# tinyarray2.net
KiCad netlist of a schematic drawn in EAGLE
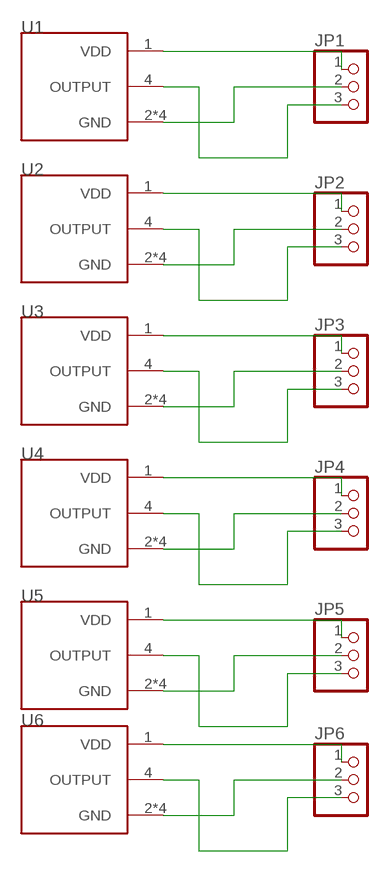
[diagram p0: schematic, sheet 1]

(export (version "E")
  (design (tool "Eeschema 10.0.6"))
  (components
    (comp (ref "JP1")
      (value "PINHD-1X3")
      (footprint "eagle-import:1X03")
      (libsource (lib "eagle-import") (part "PINHD-1X3"))
    )
    (comp (ref "JP2")
      (value "PINHD-1X3")
      (footprint "eagle-import:1X03")
      (libsource (lib "eagle-import") (part "PINHD-1X3"))
    )
    (comp (ref "JP3")
      (value "PINHD-1X3")
      (footprint "eagle-import:1X03")
      (libsource (lib "eagle-import") (part "PINHD-1X3"))
    )
    (comp (ref "JP4")
      (value "PINHD-1X3")
      (footprint "eagle-import:1X03")
      (libsource (lib "eagle-import") (part "PINHD-1X3"))
    )
    (comp (ref "JP5")
      (value "PINHD-1X3")
      (footprint "eagle-import:1X03")
      (libsource (lib "eagle-import") (part "PINHD-1X3"))
    )
    (comp (ref "JP6")
      (value "PINHD-1X3")
      (footprint "eagle-import:1X03")
      (libsource (lib "eagle-import") (part "PINHD-1X3"))
    )
    (comp (ref "U1")
      (value "CMM-3729AB-38116-TR")
      (footprint "eagle-import:XDCR_CMM-3729AB-38116-TR")
      (fields (field (name "MANUFACTURER") "CUI Inc"))
      (libsource (lib "eagle-import") (part "CMM-3729AB-38116-TR"))
    )
    (comp (ref "U2")
      (value "CMM-3729AB-38116-TR")
      (footprint "eagle-import:XDCR_CMM-3729AB-38116-TR")
      (fields (field (name "MANUFACTURER") "CUI Inc"))
      (libsource (lib "eagle-import") (part "CMM-3729AB-38116-TR"))
    )
    (comp (ref "U3")
      (value "CMM-3729AB-38116-TR")
      (footprint "eagle-import:XDCR_CMM-3729AB-38116-TR")
      (fields (field (name "MANUFACTURER") "CUI Inc"))
      (libsource (lib "eagle-import") (part "CMM-3729AB-38116-TR"))
    )
    (comp (ref "U4")
      (value "CMM-3729AB-38116-TR")
      (footprint "eagle-import:XDCR_CMM-3729AB-38116-TR")
      (fields (field (name "MANUFACTURER") "CUI Inc"))
      (libsource (lib "eagle-import") (part "CMM-3729AB-38116-TR"))
    )
    (comp (ref "U5")
      (value "CMM-3729AB-38116-TR")
      (footprint "eagle-import:XDCR_CMM-3729AB-38116-TR")
      (fields (field (name "MANUFACTURER") "CUI Inc"))
      (libsource (lib "eagle-import") (part "CMM-3729AB-38116-TR"))
    )
    (comp (ref "U6")
      (value "CMM-3729AB-38116-TR")
      (footprint "eagle-import:XDCR_CMM-3729AB-38116-TR")
      (fields (field (name "MANUFACTURER") "CUI Inc"))
      (libsource (lib "eagle-import") (part "CMM-3729AB-38116-TR"))
    )
  )
  (nets
    (net (code "1") (name "Net-(JP1-Pad2)") (class "Default")
      (node (ref "JP1") (pin "2") (pinfunction "2_2") (pintype "passive"))
      (node (ref "U1") (pin "2") (pinfunction "GND_2") (pintype "power_in"))
      (node (ref "U1") (pin "3") (pinfunction "GND_3") (pintype "power_in"))
      (node (ref "U1") (pin "5") (pinfunction "GND_5") (pintype "power_in"))
      (node (ref "U1") (pin "6") (pinfunction "GND_6") (pintype "power_in"))
    )
    (net (code "2") (name "Net-(JP2-Pad2)") (class "Default")
      (node (ref "JP2") (pin "2") (pinfunction "2_2") (pintype "passive"))
      (node (ref "U2") (pin "2") (pinfunction "GND_2") (pintype "power_in"))
      (node (ref "U2") (pin "3") (pinfunction "GND_3") (pintype "power_in"))
      (node (ref "U2") (pin "5") (pinfunction "GND_5") (pintype "power_in"))
      (node (ref "U2") (pin "6") (pinfunction "GND_6") (pintype "power_in"))
    )
    (net (code "3") (name "Net-(JP3-Pad2)") (class "Default")
      (node (ref "JP3") (pin "2") (pinfunction "2_2") (pintype "passive"))
      (node (ref "U3") (pin "2") (pinfunction "GND_2") (pintype "power_in"))
      (node (ref "U3") (pin "3") (pinfunction "GND_3") (pintype "power_in"))
      (node (ref "U3") (pin "5") (pinfunction "GND_5") (pintype "power_in"))
      (node (ref "U3") (pin "6") (pinfunction "GND_6") (pintype "power_in"))
    )
    (net (code "4") (name "Net-(JP4-Pad2)") (class "Default")
      (node (ref "JP4") (pin "2") (pinfunction "2_2") (pintype "passive"))
      (node (ref "U4") (pin "2") (pinfunction "GND_2") (pintype "power_in"))
      (node (ref "U4") (pin "3") (pinfunction "GND_3") (pintype "power_in"))
      (node (ref "U4") (pin "5") (pinfunction "GND_5") (pintype "power_in"))
      (node (ref "U4") (pin "6") (pinfunction "GND_6") (pintype "power_in"))
    )
    (net (code "5") (name "Net-(JP5-Pad2)") (class "Default")
      (node (ref "JP5") (pin "2") (pinfunction "2_2") (pintype "passive"))
      (node (ref "U5") (pin "2") (pinfunction "GND_2") (pintype "power_in"))
      (node (ref "U5") (pin "3") (pinfunction "GND_3") (pintype "power_in"))
      (node (ref "U5") (pin "5") (pinfunction "GND_5") (pintype "power_in"))
      (node (ref "U5") (pin "6") (pinfunction "GND_6") (pintype "power_in"))
    )
    (net (code "6") (name "Net-(JP6-Pad2)") (class "Default")
      (node (ref "JP6") (pin "2") (pinfunction "2_2") (pintype "passive"))
      (node (ref "U6") (pin "2") (pinfunction "GND_2") (pintype "power_in"))
      (node (ref "U6") (pin "3") (pinfunction "GND_3") (pintype "power_in"))
      (node (ref "U6") (pin "5") (pinfunction "GND_5") (pintype "power_in"))
      (node (ref "U6") (pin "6") (pinfunction "GND_6") (pintype "power_in"))
    )
    (net (code "7") (name "Net-(U1-OUTPUT)") (class "Default")
      (node (ref "JP1") (pin "3") (pinfunction "3_3") (pintype "passive"))
      (node (ref "U1") (pin "4") (pinfunction "OUTPUT_4") (pintype "output"))
    )
    (net (code "8") (name "Net-(U1-VDD)") (class "Default")
      (node (ref "JP1") (pin "1") (pinfunction "1_1") (pintype "passive"))
      (node (ref "U1") (pin "1") (pinfunction "VDD_1") (pintype "power_in"))
    )
    (net (code "9") (name "Net-(U2-OUTPUT)") (class "Default")
      (node (ref "JP2") (pin "3") (pinfunction "3_3") (pintype "passive"))
      (node (ref "U2") (pin "4") (pinfunction "OUTPUT_4") (pintype "output"))
    )
    (net (code "10") (name "Net-(U2-VDD)") (class "Default")
      (node (ref "JP2") (pin "1") (pinfunction "1_1") (pintype "passive"))
      (node (ref "U2") (pin "1") (pinfunction "VDD_1") (pintype "power_in"))
    )
    (net (code "11") (name "Net-(U3-OUTPUT)") (class "Default")
      (node (ref "JP3") (pin "3") (pinfunction "3_3") (pintype "passive"))
      (node (ref "U3") (pin "4") (pinfunction "OUTPUT_4") (pintype "output"))
    )
    (net (code "12") (name "Net-(U3-VDD)") (class "Default")
      (node (ref "JP3") (pin "1") (pinfunction "1_1") (pintype "passive"))
      (node (ref "U3") (pin "1") (pinfunction "VDD_1") (pintype "power_in"))
    )
    (net (code "13") (name "Net-(U4-OUTPUT)") (class "Default")
      (node (ref "JP4") (pin "3") (pinfunction "3_3") (pintype "passive"))
      (node (ref "U4") (pin "4") (pinfunction "OUTPUT_4") (pintype "output"))
    )
    (net (code "14") (name "Net-(U4-VDD)") (class "Default")
      (node (ref "JP4") (pin "1") (pinfunction "1_1") (pintype "passive"))
      (node (ref "U4") (pin "1") (pinfunction "VDD_1") (pintype "power_in"))
    )
    (net (code "15") (name "Net-(U5-OUTPUT)") (class "Default")
      (node (ref "JP5") (pin "3") (pinfunction "3_3") (pintype "passive"))
      (node (ref "U5") (pin "4") (pinfunction "OUTPUT_4") (pintype "output"))
    )
    (net (code "16") (name "Net-(U5-VDD)") (class "Default")
      (node (ref "JP5") (pin "1") (pinfunction "1_1") (pintype "passive"))
      (node (ref "U5") (pin "1") (pinfunction "VDD_1") (pintype "power_in"))
    )
    (net (code "17") (name "Net-(U6-OUTPUT)") (class "Default")
      (node (ref "JP6") (pin "3") (pinfunction "3_3") (pintype "passive"))
      (node (ref "U6") (pin "4") (pinfunction "OUTPUT_4") (pintype "output"))
    )
    (net (code "18") (name "Net-(U6-VDD)") (class "Default")
      (node (ref "JP6") (pin "1") (pinfunction "1_1") (pintype "passive"))
      (node (ref "U6") (pin "1") (pinfunction "VDD_1") (pintype "power_in"))
    )
  )
)
